# LEDclock_DCF77-RTC-BAT_2026-05-16.net
KiCad netlist of a schematic drawn in EasyEDA Pro
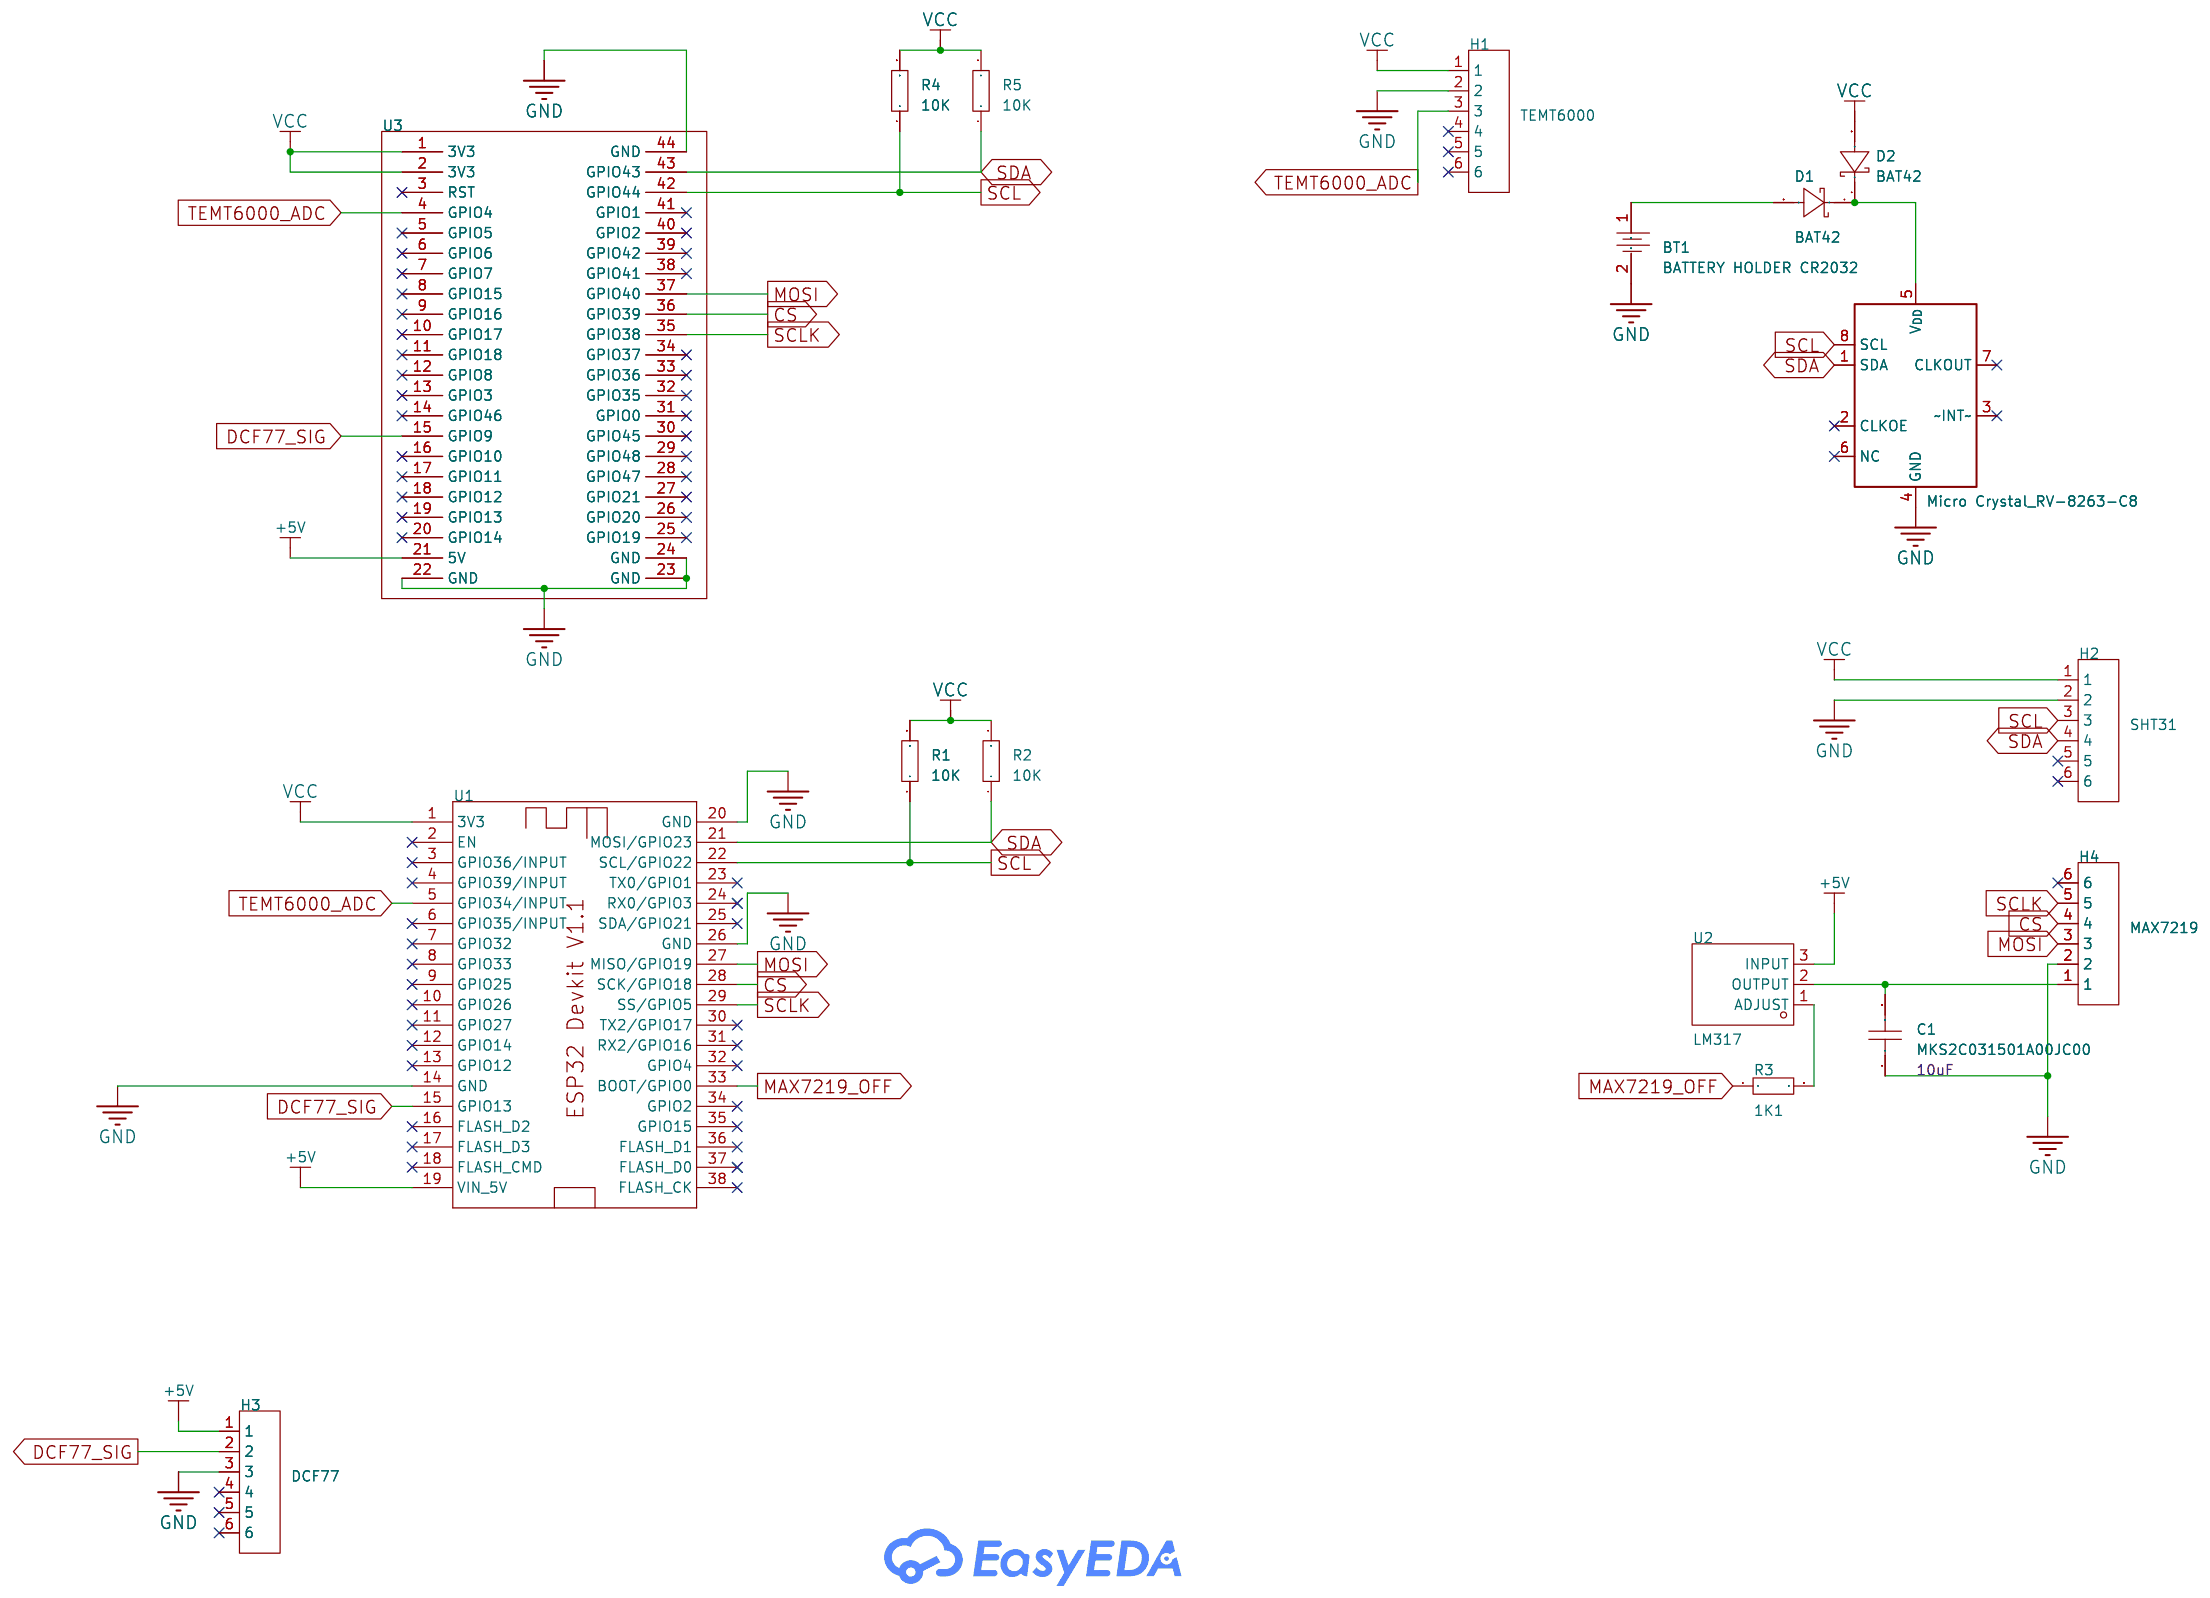
[diagram p0: schematic sheet]

(export (version "E")
  (design (tool "Eeschema 10.0.6"))
  (components
    (comp (ref "BT1")
      (value "BATTERY HOLDER CR2032")
      (footprint "easyedapro:BAT-TH_FBA25014-S02B2004K")
      (fields
        (field (name "Manufacturer Part") "FBA25014-S02B2004K")
        (field (name "Manufacturer") "TXGA(特思嘉)")
      )
      (libsource (lib "easyedapro") (part "FBA25014-S02B2004K"))
    )
    (comp (ref "C1")
      (value "MKS2C031501A00JC00")
      (footprint "easyedapro:CAP-TH_L7.2-W2.5-P5.00-D0.5-1")
      (fields (field (name "Manufacturer") "WIMA") (field (name "Capacitance") "10uF"))
      (libsource (lib "easyedapro") (part "MKS2C031501A00JC00"))
    )
    (comp (ref "D1")
      (value "BAT42")
      (footprint "easyedapro:DO-35_BD1.8-L4.1-P7.00-D0.5-RD")
      (fields (field (name "Manufacturer") "ST(意法半导体)"))
      (libsource (lib "easyedapro") (part "BAT42"))
    )
    (comp (ref "D2")
      (value "BAT42")
      (footprint "easyedapro:DO-35_BD1.8-L4.1-P7.00-D0.5-RD")
      (fields (field (name "Manufacturer") "ST(意法半导体)"))
      (libsource (lib "easyedapro") (part "BAT42"))
    )
    (comp (ref "H1")
      (value "TEMT6000")
      (footprint "easyedapro:CONN-TH_SSQ-106-03-G-S")
      (fields (field (name "Manufacturer") "SAMTEC"))
      (libsource (lib "easyedapro") (part "SSQ-106-03-G-S"))
    )
    (comp (ref "H2")
      (value "SHT31")
      (footprint "easyedapro:CONN-TH_SSQ-106-03-G-S")
      (fields (field (name "Manufacturer") "SAMTEC"))
      (libsource (lib "easyedapro") (part "SSQ-106-03-G-S"))
    )
    (comp (ref "H3")
      (value "DCF77")
      (footprint "easyedapro:CONN-TH_SSQ-106-03-G-S")
      (fields (field (name "Manufacturer") "SAMTEC"))
      (libsource (lib "easyedapro") (part "SSQ-106-03-G-S"))
    )
    (comp (ref "H4")
      (value "MAX7219")
      (footprint "easyedapro:CONN-TH_SSQ-106-03-G-S")
      (fields (field (name "Manufacturer") "SAMTEC"))
      (libsource (lib "easyedapro") (part "SSQ-106-03-G-S"))
    )
    (comp (ref "IC2")
      (value "RV-8263-C8")
      (footprint "easyedapro:Micro Crystal:RV-8263-C8")
      (libsource (lib "easyedapro") (part "Micro Crystal_RV-8263-C8"))
    )
    (comp (ref "R1") (value "10K") (footprint "easyedapro:R0603") (libsource (lib "easyedapro") (part "Res")))
    (comp (ref "R2") (value "10K") (footprint "easyedapro:R0603") (libsource (lib "easyedapro") (part "Res")))
    (comp (ref "R3") (value "1K1") (footprint "easyedapro:R0603") (libsource (lib "easyedapro") (part "Res")))
    (comp (ref "R4") (value "10K") (footprint "easyedapro:R0603") (libsource (lib "easyedapro") (part "Res")))
    (comp (ref "R5") (value "10K") (footprint "easyedapro:R0603") (libsource (lib "easyedapro") (part "Res")))
    (comp (ref "U1")
      (value "~")
      (footprint "easyedapro:ESP32-DEVKIT-V1.0-38PIN-PCB1.1")
      (libsource (lib "easyedapro") (part "ESP32-DEVKIT-V1.1"))
    )
    (comp (ref "U2")
      (value "LM317")
      (footprint "easyedapro:TO-220-3_L9.9-W4.5-P2.54-L-1")
      (fields (field (name "Manufacturer") "IDCHIP(英锐芯)"))
      (libsource (lib "easyedapro") (part "LM317_C7463411"))
    )
    (comp (ref "U3")
      (value "~")
      (footprint "easyedapro:ESP32-S3 ESP32-S3-DevKitC-1 N16R8")
      (libsource (lib "easyedapro") (part "ESP32-S3 ESP32-S3-DevKitC-1 N16R8"))
    )
  )
  (nets
    (net (code "1") (name "+5V") (class "Default")
      (node (ref "H3") (pin "1") (pinfunction "1_1") (pintype "unspecified"))
      (node (ref "U1") (pin "19") (pinfunction "VIN_5V_19") (pintype "bidirectional"))
      (node (ref "U2") (pin "3") (pinfunction "INPUT_3") (pintype "unspecified"))
      (node (ref "U3") (pin "21") (pinfunction "5V_21") (pintype "input"))
    )
    (net (code "2") (name "CS") (class "Default")
      (node (ref "H4") (pin "4") (pinfunction "4_4") (pintype "unspecified"))
      (node (ref "U1") (pin "28") (pinfunction "SCK/GPIO18_28") (pintype "bidirectional"))
      (node (ref "U3") (pin "36") (pinfunction "GPIO39_36") (pintype "input"))
    )
    (net (code "3") (name "DCF77_SIG") (class "Default")
      (node (ref "H3") (pin "2") (pinfunction "2_2") (pintype "unspecified"))
      (node (ref "U1") (pin "15") (pinfunction "GPIO13_15") (pintype "bidirectional"))
      (node (ref "U3") (pin "15") (pinfunction "GPIO9_15") (pintype "input"))
    )
    (net (code "4") (name "GND") (class "Default")
      (node (ref "BT1") (pin "2") (pinfunction "2_2") (pintype "input"))
      (node (ref "C1") (pin "1") (pinfunction "1_1") (pintype "unspecified"))
      (node (ref "H1") (pin "2") (pinfunction "2_2") (pintype "unspecified"))
      (node (ref "H2") (pin "2") (pinfunction "2_2") (pintype "unspecified"))
      (node (ref "H3") (pin "3") (pinfunction "3_3") (pintype "unspecified"))
      (node (ref "H4") (pin "2") (pinfunction "2_2") (pintype "unspecified"))
      (node (ref "IC2") (pin "4") (pinfunction "GND_4") (pintype "unspecified"))
      (node (ref "U1") (pin "14") (pinfunction "GND_14") (pintype "bidirectional"))
      (node (ref "U1") (pin "20") (pinfunction "GND_20") (pintype "bidirectional"))
      (node (ref "U1") (pin "26") (pinfunction "GND_26") (pintype "bidirectional"))
      (node (ref "U3") (pin "22") (pinfunction "GND_22") (pintype "input"))
      (node (ref "U3") (pin "23") (pinfunction "GND_23") (pintype "input"))
      (node (ref "U3") (pin "24") (pinfunction "GND_24") (pintype "input"))
      (node (ref "U3") (pin "44") (pinfunction "GND_44") (pintype "input"))
    )
    (net (code "5") (name "MAX7219_OFF") (class "Default")
      (node (ref "R3") (pin "1") (pinfunction "1_1") (pintype "input"))
      (node (ref "U1") (pin "33") (pinfunction "BOOT/GPIO0_33") (pintype "bidirectional"))
    )
    (net (code "6") (name "MOSI") (class "Default")
      (node (ref "H4") (pin "3") (pinfunction "3_3") (pintype "unspecified"))
      (node (ref "U1") (pin "27") (pinfunction "MISO/GPIO19_27") (pintype "bidirectional"))
      (node (ref "U3") (pin "37") (pinfunction "GPIO40_37") (pintype "input"))
    )
    (net (code "7") (name "Net-(D1-A)") (class "Default")
      (node (ref "BT1") (pin "1") (pinfunction "1_1") (pintype "input"))
      (node (ref "D1") (pin "2") (pinfunction "A_2") (pintype "unspecified"))
    )
    (net (code "8") (name "Net-(D1-K)") (class "Default")
      (node (ref "D1") (pin "1") (pinfunction "K_1") (pintype "unspecified"))
      (node (ref "D2") (pin "1") (pinfunction "K_1") (pintype "unspecified"))
      (node (ref "IC2") (pin "5") (pinfunction "V_{DD}_5") (pintype "unspecified"))
    )
    (net (code "9") (name "Net-(U2-ADJUST)") (class "Default")
      (node (ref "R3") (pin "2") (pinfunction "2_2") (pintype "input"))
      (node (ref "U2") (pin "1") (pinfunction "ADJUST_1") (pintype "unspecified"))
    )
    (net (code "10") (name "Net-(U2-OUTPUT)") (class "Default")
      (node (ref "C1") (pin "2") (pinfunction "2_2") (pintype "unspecified"))
      (node (ref "H4") (pin "1") (pinfunction "1_1") (pintype "unspecified"))
      (node (ref "U2") (pin "2") (pinfunction "OUTPUT_2") (pintype "unspecified"))
    )
    (net (code "11") (name "SCL") (class "Default")
      (node (ref "H2") (pin "3") (pinfunction "3_3") (pintype "unspecified"))
      (node (ref "IC2") (pin "8") (pinfunction "SCL_8") (pintype "input"))
      (node (ref "R1") (pin "1") (pinfunction "1_1") (pintype "input"))
      (node (ref "R4") (pin "1") (pinfunction "1_1") (pintype "input"))
      (node (ref "U1") (pin "22") (pinfunction "SCL/GPIO22_22") (pintype "bidirectional"))
      (node (ref "U3") (pin "42") (pinfunction "GPIO44_42") (pintype "input"))
    )
    (net (code "12") (name "SCLK") (class "Default")
      (node (ref "H4") (pin "5") (pinfunction "5_5") (pintype "unspecified"))
      (node (ref "U1") (pin "29") (pinfunction "SS/GPIO5_29") (pintype "bidirectional"))
      (node (ref "U3") (pin "35") (pinfunction "GPIO38_35") (pintype "input"))
    )
    (net (code "13") (name "SDA") (class "Default")
      (node (ref "H2") (pin "4") (pinfunction "4_4") (pintype "unspecified"))
      (node (ref "IC2") (pin "1") (pinfunction "SDA_1") (pintype "bidirectional"))
      (node (ref "R2") (pin "1") (pinfunction "1_1") (pintype "input"))
      (node (ref "R5") (pin "1") (pinfunction "1_1") (pintype "input"))
      (node (ref "U1") (pin "21") (pinfunction "MOSI/GPIO23_21") (pintype "bidirectional"))
      (node (ref "U3") (pin "43") (pinfunction "GPIO43_43") (pintype "input"))
    )
    (net (code "14") (name "TEMT6000_ADC") (class "Default")
      (node (ref "H1") (pin "3") (pinfunction "3_3") (pintype "unspecified"))
      (node (ref "U1") (pin "5") (pinfunction "GPIO34/INPUT_5") (pintype "bidirectional"))
      (node (ref "U3") (pin "4") (pinfunction "GPIO4_4") (pintype "input"))
    )
    (net (code "15") (name "VCC") (class "Default")
      (node (ref "D2") (pin "2") (pinfunction "A_2") (pintype "unspecified"))
      (node (ref "H1") (pin "1") (pinfunction "1_1") (pintype "unspecified"))
      (node (ref "H2") (pin "1") (pinfunction "1_1") (pintype "unspecified"))
      (node (ref "R1") (pin "2") (pinfunction "2_2") (pintype "input"))
      (node (ref "R2") (pin "2") (pinfunction "2_2") (pintype "input"))
      (node (ref "R4") (pin "2") (pinfunction "2_2") (pintype "input"))
      (node (ref "R5") (pin "2") (pinfunction "2_2") (pintype "input"))
      (node (ref "U1") (pin "1") (pinfunction "3V3_1") (pintype "bidirectional"))
      (node (ref "U3") (pin "1") (pinfunction "3V3_1") (pintype "input"))
      (node (ref "U3") (pin "2") (pinfunction "3V3_2") (pintype "input"))
    )
    (net (code "16") (name "unconnected-(H1-Pad4)") (class "Default")
      (node (ref "H1") (pin "4") (pinfunction "4_4") (pintype "unspecified+no_connect"))
    )
    (net (code "17") (name "unconnected-(H1-Pad5)") (class "Default")
      (node (ref "H1") (pin "5") (pinfunction "5_5") (pintype "unspecified+no_connect"))
    )
    (net (code "18") (name "unconnected-(H1-Pad6)") (class "Default")
      (node (ref "H1") (pin "6") (pinfunction "6_6") (pintype "unspecified+no_connect"))
    )
    (net (code "19") (name "unconnected-(H2-Pad5)") (class "Default")
      (node (ref "H2") (pin "5") (pinfunction "5_5") (pintype "unspecified+no_connect"))
    )
    (net (code "20") (name "unconnected-(H2-Pad6)") (class "Default")
      (node (ref "H2") (pin "6") (pinfunction "6_6") (pintype "unspecified+no_connect"))
    )
    (net (code "21") (name "unconnected-(H3-Pad4)") (class "Default")
      (node (ref "H3") (pin "4") (pinfunction "4_4") (pintype "unspecified+no_connect"))
    )
    (net (code "22") (name "unconnected-(H3-Pad5)") (class "Default")
      (node (ref "H3") (pin "5") (pinfunction "5_5") (pintype "unspecified+no_connect"))
    )
    (net (code "23") (name "unconnected-(H3-Pad6)") (class "Default")
      (node (ref "H3") (pin "6") (pinfunction "6_6") (pintype "unspecified+no_connect"))
    )
    (net (code "24") (name "unconnected-(H4-Pad6)") (class "Default")
      (node (ref "H4") (pin "6") (pinfunction "6_6") (pintype "unspecified+no_connect"))
    )
    (net (code "25") (name "unconnected-(IC2-CLKOE-Pad2)") (class "Default")
      (node (ref "IC2") (pin "2") (pinfunction "CLKOE_2") (pintype "input+no_connect"))
    )
    (net (code "26") (name "unconnected-(IC2-CLKOUT-Pad7)") (class "Default")
      (node (ref "IC2") (pin "7") (pinfunction "CLKOUT_7") (pintype "output+no_connect"))
    )
    (net (code "27") (name "unconnected-(IC2-NC-Pad6)") (class "Default")
      (node (ref "IC2") (pin "6") (pinfunction "NC_6") (pintype "unspecified+no_connect"))
    )
    (net (code "28") (name "unconnected-(IC2-~INT~-Pad3)") (class "Default")
      (node (ref "IC2") (pin "3") (pinfunction "~INT~_3") (pintype "output+no_connect"))
    )
    (net (code "29") (name "unconnected-(U1-EN-Pad2)") (class "Default")
      (node (ref "U1") (pin "2") (pinfunction "EN_2") (pintype "bidirectional+no_connect"))
    )
    (net (code "30") (name "unconnected-(U1-FLASH_CK-Pad38)") (class "Default")
      (node (ref "U1") (pin "38") (pinfunction "FLASH_CK_38") (pintype "bidirectional+no_connect"))
    )
    (net (code "31") (name "unconnected-(U1-FLASH_CMD-Pad18)") (class "Default")
      (node (ref "U1") (pin "18") (pinfunction "FLASH_CMD_18") (pintype "bidirectional+no_connect"))
    )
    (net (code "32") (name "unconnected-(U1-FLASH_D0-Pad37)") (class "Default")
      (node (ref "U1") (pin "37") (pinfunction "FLASH_D0_37") (pintype "bidirectional+no_connect"))
    )
    (net (code "33") (name "unconnected-(U1-FLASH_D1-Pad36)") (class "Default")
      (node (ref "U1") (pin "36") (pinfunction "FLASH_D1_36") (pintype "bidirectional+no_connect"))
    )
    (net (code "34") (name "unconnected-(U1-FLASH_D2-Pad16)") (class "Default")
      (node (ref "U1") (pin "16") (pinfunction "FLASH_D2_16") (pintype "bidirectional+no_connect"))
    )
    (net (code "35") (name "unconnected-(U1-FLASH_D3-Pad17)") (class "Default")
      (node (ref "U1") (pin "17") (pinfunction "FLASH_D3_17") (pintype "bidirectional+no_connect"))
    )
    (net (code "36") (name "unconnected-(U1-GPIO2-Pad34)") (class "Default")
      (node (ref "U1") (pin "34") (pinfunction "GPIO2_34") (pintype "bidirectional+no_connect"))
    )
    (net (code "37") (name "unconnected-(U1-GPIO4-Pad32)") (class "Default")
      (node (ref "U1") (pin "32") (pinfunction "GPIO4_32") (pintype "bidirectional+no_connect"))
    )
    (net (code "38") (name "unconnected-(U1-GPIO12-Pad13)") (class "Default")
      (node (ref "U1") (pin "13") (pinfunction "GPIO12_13") (pintype "bidirectional+no_connect"))
    )
    (net (code "39") (name "unconnected-(U1-GPIO14-Pad12)") (class "Default")
      (node (ref "U1") (pin "12") (pinfunction "GPIO14_12") (pintype "bidirectional+no_connect"))
    )
    (net (code "40") (name "unconnected-(U1-GPIO15-Pad35)") (class "Default")
      (node (ref "U1") (pin "35") (pinfunction "GPIO15_35") (pintype "bidirectional+no_connect"))
    )
    (net (code "41") (name "unconnected-(U1-GPIO25-Pad9)") (class "Default")
      (node (ref "U1") (pin "9") (pinfunction "GPIO25_9") (pintype "bidirectional+no_connect"))
    )
    (net (code "42") (name "unconnected-(U1-GPIO26-Pad10)") (class "Default")
      (node (ref "U1") (pin "10") (pinfunction "GPIO26_10") (pintype "bidirectional+no_connect"))
    )
    (net (code "43") (name "unconnected-(U1-GPIO27-Pad11)") (class "Default")
      (node (ref "U1") (pin "11") (pinfunction "GPIO27_11") (pintype "bidirectional+no_connect"))
    )
    (net (code "44") (name "unconnected-(U1-GPIO32-Pad7)") (class "Default")
      (node (ref "U1") (pin "7") (pinfunction "GPIO32_7") (pintype "bidirectional+no_connect"))
    )
    (net (code "45") (name "unconnected-(U1-GPIO33-Pad8)") (class "Default")
      (node (ref "U1") (pin "8") (pinfunction "GPIO33_8") (pintype "bidirectional+no_connect"))
    )
    (net (code "46") (name "unconnected-(U1-GPIO35{slash}INPUT-Pad6)") (class "Default")
      (node (ref "U1") (pin "6") (pinfunction "GPIO35/INPUT_6") (pintype "bidirectional+no_connect"))
    )
    (net (code "47") (name "unconnected-(U1-GPIO36{slash}INPUT-Pad3)") (class "Default")
      (node (ref "U1") (pin "3") (pinfunction "GPIO36/INPUT_3") (pintype "bidirectional+no_connect"))
    )
    (net (code "48") (name "unconnected-(U1-GPIO39{slash}INPUT-Pad4)") (class "Default")
      (node (ref "U1") (pin "4") (pinfunction "GPIO39/INPUT_4") (pintype "bidirectional+no_connect"))
    )
    (net (code "49") (name "unconnected-(U1-RX0{slash}GPIO3-Pad24)") (class "Default")
      (node (ref "U1") (pin "24") (pinfunction "RX0/GPIO3_24") (pintype "bidirectional+no_connect"))
    )
    (net (code "50") (name "unconnected-(U1-RX2{slash}GPIO16-Pad31)") (class "Default")
      (node (ref "U1") (pin "31") (pinfunction "RX2/GPIO16_31") (pintype "bidirectional+no_connect"))
    )
    (net (code "51") (name "unconnected-(U1-SDA{slash}GPIO21-Pad25)") (class "Default")
      (node (ref "U1") (pin "25") (pinfunction "SDA/GPIO21_25") (pintype "bidirectional+no_connect"))
    )
    (net (code "52") (name "unconnected-(U1-TX0{slash}GPIO1-Pad23)") (class "Default")
      (node (ref "U1") (pin "23") (pinfunction "TX0/GPIO1_23") (pintype "bidirectional+no_connect"))
    )
    (net (code "53") (name "unconnected-(U1-TX2{slash}GPIO17-Pad30)") (class "Default")
      (node (ref "U1") (pin "30") (pinfunction "TX2/GPIO17_30") (pintype "bidirectional+no_connect"))
    )
    (net (code "54") (name "unconnected-(U3-GPIO0-Pad31)") (class "Default")
      (node (ref "U3") (pin "31") (pinfunction "GPIO0_31") (pintype "input+no_connect"))
    )
    (net (code "55") (name "unconnected-(U3-GPIO1-Pad41)") (class "Default")
      (node (ref "U3") (pin "41") (pinfunction "GPIO1_41") (pintype "input+no_connect"))
    )
    (net (code "56") (name "unconnected-(U3-GPIO2-Pad40)") (class "Default")
      (node (ref "U3") (pin "40") (pinfunction "GPIO2_40") (pintype "input+no_connect"))
    )
    (net (code "57") (name "unconnected-(U3-GPIO3-Pad13)") (class "Default")
      (node (ref "U3") (pin "13") (pinfunction "GPIO3_13") (pintype "input+no_connect"))
    )
    (net (code "58") (name "unconnected-(U3-GPIO5-Pad5)") (class "Default")
      (node (ref "U3") (pin "5") (pinfunction "GPIO5_5") (pintype "input+no_connect"))
    )
    (net (code "59") (name "unconnected-(U3-GPIO6-Pad6)") (class "Default")
      (node (ref "U3") (pin "6") (pinfunction "GPIO6_6") (pintype "input+no_connect"))
    )
    (net (code "60") (name "unconnected-(U3-GPIO7-Pad7)") (class "Default")
      (node (ref "U3") (pin "7") (pinfunction "GPIO7_7") (pintype "input+no_connect"))
    )
    (net (code "61") (name "unconnected-(U3-GPIO8-Pad12)") (class "Default")
      (node (ref "U3") (pin "12") (pinfunction "GPIO8_12") (pintype "input+no_connect"))
    )
    (net (code "62") (name "unconnected-(U3-GPIO10-Pad16)") (class "Default")
      (node (ref "U3") (pin "16") (pinfunction "GPIO10_16") (pintype "input+no_connect"))
    )
    (net (code "63") (name "unconnected-(U3-GPIO11-Pad17)") (class "Default")
      (node (ref "U3") (pin "17") (pinfunction "GPIO11_17") (pintype "input+no_connect"))
    )
    (net (code "64") (name "unconnected-(U3-GPIO12-Pad18)") (class "Default")
      (node (ref "U3") (pin "18") (pinfunction "GPIO12_18") (pintype "input+no_connect"))
    )
    (net (code "65") (name "unconnected-(U3-GPIO13-Pad19)") (class "Default")
      (node (ref "U3") (pin "19") (pinfunction "GPIO13_19") (pintype "input+no_connect"))
    )
    (net (code "66") (name "unconnected-(U3-GPIO14-Pad20)") (class "Default")
      (node (ref "U3") (pin "20") (pinfunction "GPIO14_20") (pintype "input+no_connect"))
    )
    (net (code "67") (name "unconnected-(U3-GPIO15-Pad8)") (class "Default")
      (node (ref "U3") (pin "8") (pinfunction "GPIO15_8") (pintype "input+no_connect"))
    )
    (net (code "68") (name "unconnected-(U3-GPIO16-Pad9)") (class "Default")
      (node (ref "U3") (pin "9") (pinfunction "GPIO16_9") (pintype "input+no_connect"))
    )
    (net (code "69") (name "unconnected-(U3-GPIO17-Pad10)") (class "Default")
      (node (ref "U3") (pin "10") (pinfunction "GPIO17_10") (pintype "input+no_connect"))
    )
    (net (code "70") (name "unconnected-(U3-GPIO18-Pad11)") (class "Default")
      (node (ref "U3") (pin "11") (pinfunction "GPIO18_11") (pintype "input+no_connect"))
    )
    (net (code "71") (name "unconnected-(U3-GPIO19-Pad25)") (class "Default")
      (node (ref "U3") (pin "25") (pinfunction "GPIO19_25") (pintype "input+no_connect"))
    )
    (net (code "72") (name "unconnected-(U3-GPIO20-Pad26)") (class "Default")
      (node (ref "U3") (pin "26") (pinfunction "GPIO20_26") (pintype "input+no_connect"))
    )
    (net (code "73") (name "unconnected-(U3-GPIO21-Pad27)") (class "Default")
      (node (ref "U3") (pin "27") (pinfunction "GPIO21_27") (pintype "input+no_connect"))
    )
    (net (code "74") (name "unconnected-(U3-GPIO35-Pad32)") (class "Default")
      (node (ref "U3") (pin "32") (pinfunction "GPIO35_32") (pintype "input+no_connect"))
    )
    (net (code "75") (name "unconnected-(U3-GPIO36-Pad33)") (class "Default")
      (node (ref "U3") (pin "33") (pinfunction "GPIO36_33") (pintype "input+no_connect"))
    )
    (net (code "76") (name "unconnected-(U3-GPIO37-Pad34)") (class "Default")
      (node (ref "U3") (pin "34") (pinfunction "GPIO37_34") (pintype "input+no_connect"))
    )
    (net (code "77") (name "unconnected-(U3-GPIO41-Pad38)") (class "Default")
      (node (ref "U3") (pin "38") (pinfunction "GPIO41_38") (pintype "input+no_connect"))
    )
    (net (code "78") (name "unconnected-(U3-GPIO42-Pad39)") (class "Default")
      (node (ref "U3") (pin "39") (pinfunction "GPIO42_39") (pintype "input+no_connect"))
    )
    (net (code "79") (name "unconnected-(U3-GPIO45-Pad30)") (class "Default")
      (node (ref "U3") (pin "30") (pinfunction "GPIO45_30") (pintype "input+no_connect"))
    )
    (net (code "80") (name "unconnected-(U3-GPIO46-Pad14)") (class "Default")
      (node (ref "U3") (pin "14") (pinfunction "GPIO46_14") (pintype "input+no_connect"))
    )
    (net (code "81") (name "unconnected-(U3-GPIO47-Pad28)") (class "Default")
      (node (ref "U3") (pin "28") (pinfunction "GPIO47_28") (pintype "input+no_connect"))
    )
    (net (code "82") (name "unconnected-(U3-GPIO48-Pad29)") (class "Default")
      (node (ref "U3") (pin "29") (pinfunction "GPIO48_29") (pintype "input+no_connect"))
    )
    (net (code "83") (name "unconnected-(U3-RST-Pad3)") (class "Default")
      (node (ref "U3") (pin "3") (pinfunction "RST_3") (pintype "input+no_connect"))
    )
  )
)
